# RaspPi_PCB.net
KiCad netlist of a schematic drawn in EAGLE
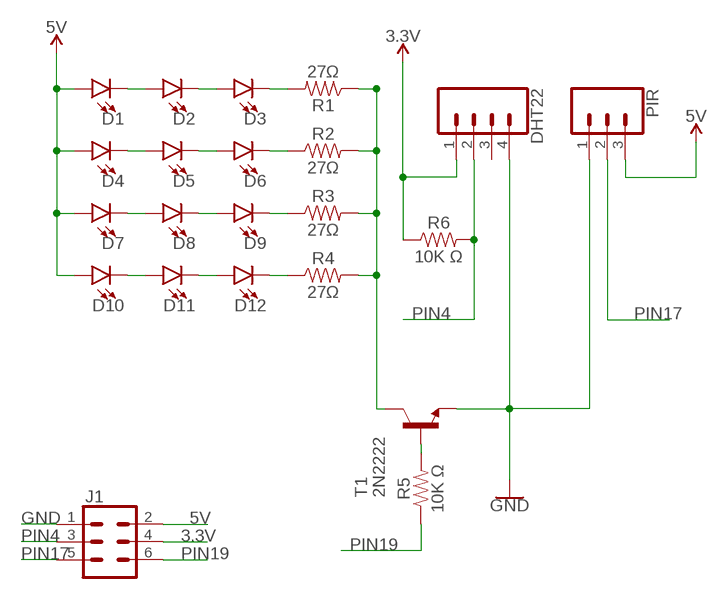
[diagram p0: schematic, sheet 1]

(export (version "E")
  (design (tool "Eeschema 10.0.6"))
  (components
    (comp (ref "D1")
      (value "LED5MM")
      (footprint "eagle-import:LED_5MM")
      (libsource (lib "eagle-import") (part "LED5MM"))
    )
    (comp (ref "D2")
      (value "LED5MM")
      (footprint "eagle-import:LED_5MM")
      (libsource (lib "eagle-import") (part "LED5MM"))
    )
    (comp (ref "D3")
      (value "LED5MM")
      (footprint "eagle-import:LED_5MM")
      (libsource (lib "eagle-import") (part "LED5MM"))
    )
    (comp (ref "D4")
      (value "LED5MM")
      (footprint "eagle-import:LED_5MM")
      (libsource (lib "eagle-import") (part "LED5MM"))
    )
    (comp (ref "D5")
      (value "LED5MM")
      (footprint "eagle-import:LED_5MM")
      (libsource (lib "eagle-import") (part "LED5MM"))
    )
    (comp (ref "D6")
      (value "LED5MM")
      (footprint "eagle-import:LED_5MM")
      (libsource (lib "eagle-import") (part "LED5MM"))
    )
    (comp (ref "D7")
      (value "LED5MM")
      (footprint "eagle-import:LED_5MM")
      (libsource (lib "eagle-import") (part "LED5MM"))
    )
    (comp (ref "D8")
      (value "LED5MM")
      (footprint "eagle-import:LED_5MM")
      (libsource (lib "eagle-import") (part "LED5MM"))
    )
    (comp (ref "D9")
      (value "LED5MM")
      (footprint "eagle-import:LED_5MM")
      (libsource (lib "eagle-import") (part "LED5MM"))
    )
    (comp (ref "D10")
      (value "LED5MM")
      (footprint "eagle-import:LED_5MM")
      (libsource (lib "eagle-import") (part "LED5MM"))
    )
    (comp (ref "D11")
      (value "LED5MM")
      (footprint "eagle-import:LED_5MM")
      (libsource (lib "eagle-import") (part "LED5MM"))
    )
    (comp (ref "D12")
      (value "LED5MM")
      (footprint "eagle-import:LED_5MM")
      (libsource (lib "eagle-import") (part "LED5MM"))
    )
    (comp (ref "DHT22")
      (value "CONN_04LONGPADS")
      (footprint "eagle-import:1X04_LONGPADS")
      (libsource (lib "eagle-import") (part "CONN_04LONGPADS"))
    )
    (comp (ref "J1")
      (value "CONN_03X2SHROUD")
      (footprint "eagle-import:2X3-SHROUDED")
      (libsource (lib "eagle-import") (part "CONN_03X2SHROUD"))
    )
    (comp (ref "PIR")
      (value "CONN_03LONGPADS")
      (footprint "eagle-import:1X03_LONGPADS")
      (libsource (lib "eagle-import") (part "CONN_03LONGPADS"))
    )
    (comp (ref "R1")
      (value "27Ω")
      (footprint "eagle-import:AXIAL-0.3-KIT")
      (libsource (lib "eagle-import") (part "10OHM-HORIZ_KIT-1/4W-1%"))
    )
    (comp (ref "R2")
      (value "27Ω")
      (footprint "eagle-import:AXIAL-0.3-KIT")
      (libsource (lib "eagle-import") (part "10OHM-HORIZ_KIT-1/4W-1%"))
    )
    (comp (ref "R3")
      (value "27Ω")
      (footprint "eagle-import:AXIAL-0.3-KIT")
      (libsource (lib "eagle-import") (part "10OHM-HORIZ_KIT-1/4W-1%"))
    )
    (comp (ref "R4")
      (value "27Ω")
      (footprint "eagle-import:AXIAL-0.3-KIT")
      (libsource (lib "eagle-import") (part "10OHM-HORIZ_KIT-1/4W-1%"))
    )
    (comp (ref "R5")
      (value "10K Ω")
      (footprint "eagle-import:AXIAL-0.3-KIT")
      (libsource (lib "eagle-import") (part "10OHM-HORIZ_KIT-1/4W-1%"))
    )
    (comp (ref "R6")
      (value "10K Ω")
      (footprint "eagle-import:AXIAL-0.3-KIT")
      (libsource (lib "eagle-import") (part "10OHM-HORIZ_KIT-1/4W-1%"))
    )
    (comp (ref "T1")
      (value "2N2222")
      (footprint "eagle-import:TO92-EBC-OVAL")
      (libsource (lib "eagle-import") (part "2N2222"))
    )
  )
  (nets
    (net (code "1") (name "/PIN4") (class "Default")
      (node (ref "DHT22") (pin "2") (pinfunction "2_2") (pintype "passive"))
      (node (ref "J1") (pin "3") (pinfunction "3_3") (pintype "bidirectional"))
      (node (ref "R6") (pin "P$2") (pinfunction "2_P$2") (pintype "passive"))
    )
    (net (code "2") (name "/PIN17") (class "Default")
      (node (ref "J1") (pin "5") (pinfunction "5_5") (pintype "bidirectional"))
      (node (ref "PIR") (pin "2") (pinfunction "2_2") (pintype "passive"))
    )
    (net (code "3") (name "/PIN19") (class "Default")
      (node (ref "J1") (pin "6") (pinfunction "6_6") (pintype "bidirectional"))
      (node (ref "R5") (pin "P$1") (pinfunction "1_P$1") (pintype "passive"))
    )
    (net (code "4") (name "3.3V") (class "Default")
      (node (ref "DHT22") (pin "1") (pinfunction "1_1") (pintype "passive"))
      (node (ref "J1") (pin "4") (pinfunction "4_4") (pintype "bidirectional"))
      (node (ref "R6") (pin "P$1") (pinfunction "1_P$1") (pintype "passive"))
    )
    (net (code "5") (name "5V") (class "Default")
      (node (ref "D1") (pin "A") (pinfunction "A_A") (pintype "passive"))
      (node (ref "D10") (pin "A") (pinfunction "A_A") (pintype "passive"))
      (node (ref "D4") (pin "A") (pinfunction "A_A") (pintype "passive"))
      (node (ref "D7") (pin "A") (pinfunction "A_A") (pintype "passive"))
      (node (ref "J1") (pin "2") (pinfunction "2_2") (pintype "bidirectional"))
      (node (ref "PIR") (pin "3") (pinfunction "3_3") (pintype "passive"))
    )
    (net (code "6") (name "GND") (class "Default")
      (node (ref "DHT22") (pin "4") (pinfunction "4_4") (pintype "passive"))
      (node (ref "J1") (pin "1") (pinfunction "1_1") (pintype "bidirectional"))
      (node (ref "PIR") (pin "1") (pinfunction "1_1") (pintype "passive"))
      (node (ref "T1") (pin "E") (pinfunction "E_E") (pintype "passive"))
    )
    (net (code "7") (name "Net-(D1-C)") (class "Default")
      (node (ref "D1") (pin "K") (pinfunction "C_K") (pintype "passive"))
      (node (ref "D2") (pin "A") (pinfunction "A_A") (pintype "passive"))
    )
    (net (code "8") (name "Net-(D2-C)") (class "Default")
      (node (ref "D2") (pin "K") (pinfunction "C_K") (pintype "passive"))
      (node (ref "D3") (pin "A") (pinfunction "A_A") (pintype "passive"))
    )
    (net (code "9") (name "Net-(D3-C)") (class "Default")
      (node (ref "D3") (pin "K") (pinfunction "C_K") (pintype "passive"))
      (node (ref "R1") (pin "P$2") (pinfunction "2_P$2") (pintype "passive"))
    )
    (net (code "10") (name "Net-(D4-C)") (class "Default")
      (node (ref "D4") (pin "K") (pinfunction "C_K") (pintype "passive"))
      (node (ref "D5") (pin "A") (pinfunction "A_A") (pintype "passive"))
    )
    (net (code "11") (name "Net-(D5-C)") (class "Default")
      (node (ref "D5") (pin "K") (pinfunction "C_K") (pintype "passive"))
      (node (ref "D6") (pin "A") (pinfunction "A_A") (pintype "passive"))
    )
    (net (code "12") (name "Net-(D6-C)") (class "Default")
      (node (ref "D6") (pin "K") (pinfunction "C_K") (pintype "passive"))
      (node (ref "R2") (pin "P$1") (pinfunction "1_P$1") (pintype "passive"))
    )
    (net (code "13") (name "Net-(D7-C)") (class "Default")
      (node (ref "D7") (pin "K") (pinfunction "C_K") (pintype "passive"))
      (node (ref "D8") (pin "A") (pinfunction "A_A") (pintype "passive"))
    )
    (net (code "14") (name "Net-(D8-C)") (class "Default")
      (node (ref "D8") (pin "K") (pinfunction "C_K") (pintype "passive"))
      (node (ref "D9") (pin "A") (pinfunction "A_A") (pintype "passive"))
    )
    (net (code "15") (name "Net-(D9-C)") (class "Default")
      (node (ref "D9") (pin "K") (pinfunction "C_K") (pintype "passive"))
      (node (ref "R3") (pin "P$1") (pinfunction "1_P$1") (pintype "passive"))
    )
    (net (code "16") (name "Net-(D10-C)") (class "Default")
      (node (ref "D10") (pin "K") (pinfunction "C_K") (pintype "passive"))
      (node (ref "D11") (pin "A") (pinfunction "A_A") (pintype "passive"))
    )
    (net (code "17") (name "Net-(D11-C)") (class "Default")
      (node (ref "D11") (pin "K") (pinfunction "C_K") (pintype "passive"))
      (node (ref "D12") (pin "A") (pinfunction "A_A") (pintype "passive"))
    )
    (net (code "18") (name "Net-(D12-C)") (class "Default")
      (node (ref "D12") (pin "K") (pinfunction "C_K") (pintype "passive"))
      (node (ref "R4") (pin "P$1") (pinfunction "1_P$1") (pintype "passive"))
    )
    (net (code "19") (name "Net-(R1-1)") (class "Default")
      (node (ref "R1") (pin "P$1") (pinfunction "1_P$1") (pintype "passive"))
      (node (ref "R2") (pin "P$2") (pinfunction "2_P$2") (pintype "passive"))
      (node (ref "R3") (pin "P$2") (pinfunction "2_P$2") (pintype "passive"))
      (node (ref "R4") (pin "P$2") (pinfunction "2_P$2") (pintype "passive"))
      (node (ref "T1") (pin "C") (pinfunction "C_C") (pintype "passive"))
    )
    (net (code "20") (name "Net-(R5-2)") (class "Default")
      (node (ref "R5") (pin "P$2") (pinfunction "2_P$2") (pintype "passive"))
      (node (ref "T1") (pin "B") (pinfunction "B_B") (pintype "passive"))
    )
    (net (code "21") (name "unconnected-(DHT22-Pad3)") (class "Default")
      (node (ref "DHT22") (pin "3") (pinfunction "3_3") (pintype "passive"))
    )
  )
)
